# RogoIR.net
KiCad netlist of a schematic drawn in Altium Designer
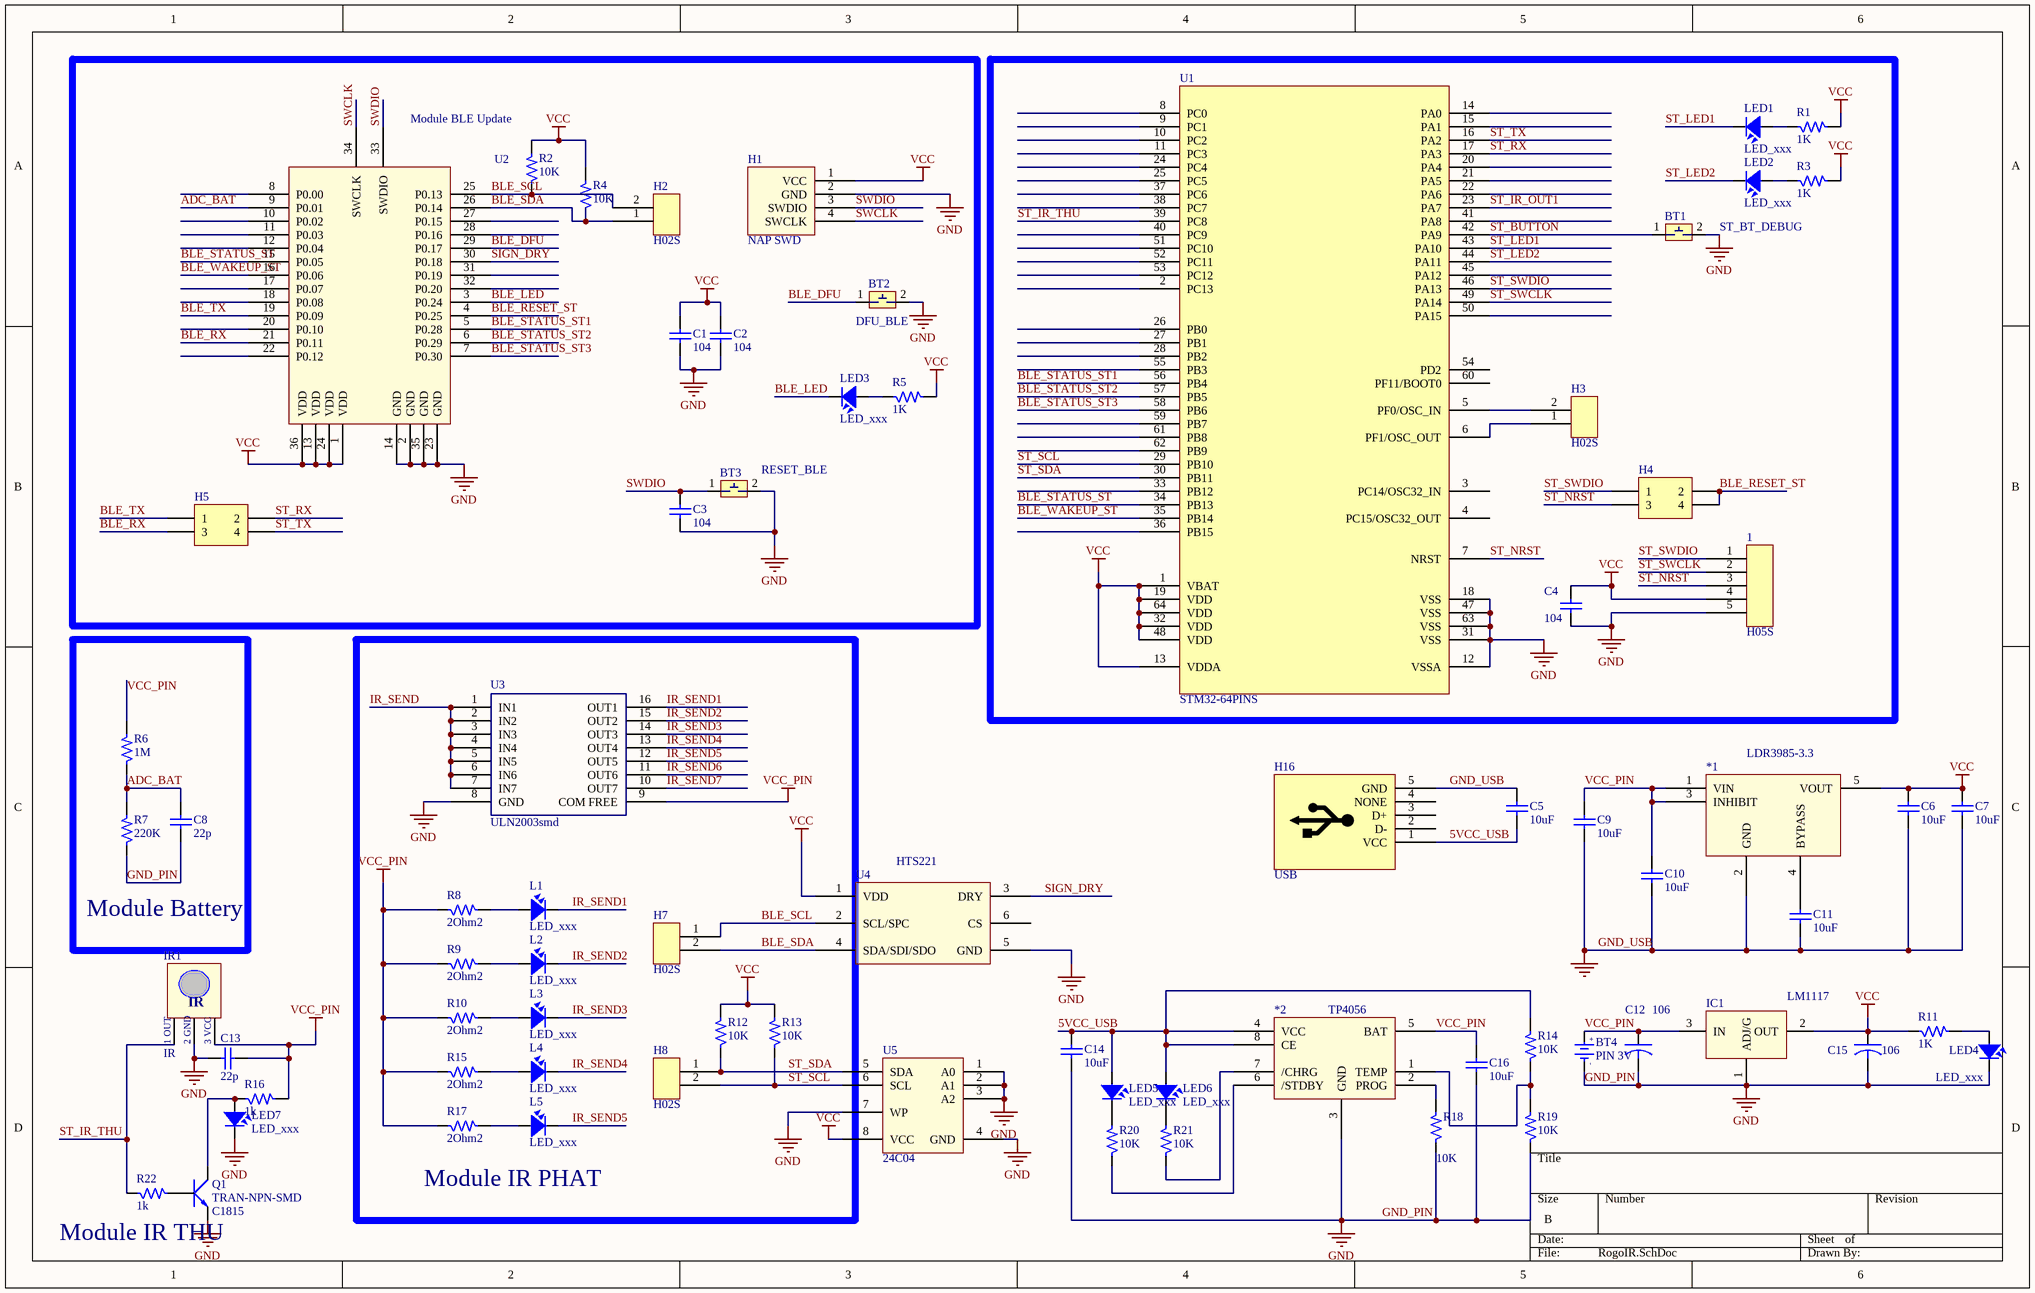
[diagram p0: RogoIR.SchDoc]

(export (version "E")
  (design (tool "Eeschema 10.0.6"))
  (components
    (comp (ref "*1")
      (value "LDR3985-3.3")
      (footprint "LDR3985-3.3")
      (libsource (lib "AngleVu") (part "LDR3985-3.3"))
    )
    (comp (ref "*2") (value "TP4056") (footprint "TP4056") (libsource (lib "AngleVu") (part "TP4056")))
    (comp (ref "1")
      (value "H05S")
      (footprint "H05SA")
      (description "HEADER, SINGLE")
      (libsource (lib "AngleVu") (part "H05S"))
    )
    (comp (ref "BT1")
      (value "ST_BT_DEBUG")
      (footprint "SW2-SMD")
      (libsource (lib "BNTLIB") (part "BUTTON 2 PIN"))
    )
    (comp (ref "BT2")
      (value "DFU_BLE")
      (footprint "SW2-SMD")
      (libsource (lib "BNTLIB") (part "BUTTON 2 PIN"))
    )
    (comp (ref "BT3")
      (value "RESET_BLE")
      (footprint "SW2-SMD")
      (libsource (lib "BNTLIB") (part "BUTTON 2 PIN"))
    )
    (comp (ref "BT4")
      (value "PIN 3V")
      (footprint "H02MA")
      (description "Battery 3VDC")
      (libsource (lib "BNTLIB") (part "PIN 3V"))
    )
    (comp (ref "C1") (value "104") (footprint "0805") (libsource (lib "BNTLIB") (part "Cap")))
    (comp (ref "C2") (value "104") (footprint "0805") (libsource (lib "BNTLIB") (part "Cap")))
    (comp (ref "C3") (value "104") (footprint "0805") (libsource (lib "BNTLIB") (part "Cap")))
    (comp (ref "C4") (value "104") (footprint "0805") (libsource (lib "BNTLIB") (part "Cap")))
    (comp (ref "C5") (value "10uF") (footprint "0805") (libsource (lib "BNTLIB") (part "Cap")))
    (comp (ref "C6") (value "10uF") (footprint "0805") (libsource (lib "BNTLIB") (part "Cap")))
    (comp (ref "C7") (value "10uF") (footprint "0805") (libsource (lib "BNTLIB") (part "Cap")))
    (comp (ref "C8") (value "22p") (footprint "0805") (libsource (lib "BNTLIB") (part "Cap")))
    (comp (ref "C9") (value "10uF") (footprint "0805") (libsource (lib "BNTLIB") (part "Cap")))
    (comp (ref "C10") (value "10uF") (footprint "0805") (libsource (lib "BNTLIB") (part "Cap")))
    (comp (ref "C11") (value "10uF") (footprint "0805") (libsource (lib "BNTLIB") (part "Cap")))
    (comp (ref "C12")
      (value "106")
      (footprint "1206")
      (description "Capacitor")
      (libsource (lib "BNTLIB") (part "CAPACITOR"))
    )
    (comp (ref "C13") (value "22p") (footprint "0805") (libsource (lib "BNTLIB") (part "Cap")))
    (comp (ref "C14") (value "10uF") (footprint "0805") (libsource (lib "BNTLIB") (part "Cap")))
    (comp (ref "C15")
      (value "106")
      (footprint "1206")
      (description "Capacitor")
      (libsource (lib "BNTLIB") (part "CAPACITOR"))
    )
    (comp (ref "C16") (value "10uF") (footprint "0805") (libsource (lib "BNTLIB") (part "Cap")))
    (comp (ref "H1") (value "NAP SWD") (footprint "H04SA") (libsource (lib "AngleVu") (part "NAP SWD")))
    (comp (ref "H2")
      (value "H02S")
      (footprint "H02SA")
      (description "HEADER, SINGLE")
      (libsource (lib "") (part "H02S_1"))
    )
    (comp (ref "H3")
      (value "H02S")
      (footprint "H02SA")
      (description "HEADER, SINGLE")
      (libsource (lib "") (part "H02S_1"))
    )
    (comp (ref "H4")
      (value "H04M")
      (footprint "HDR2X2")
      (description "HEADER, DOUBLE")
      (fields (field (name "PUBLISHER") "Altium Limited"))
      (libsource (lib "AngleVu") (part "H04M"))
    )
    (comp (ref "H5")
      (value "H04M")
      (footprint "HDR2X2")
      (description "HEADER, DOUBLE")
      (fields (field (name "PUBLISHER") "Altium Limited"))
      (libsource (lib "AngleVu") (part "H04M"))
    )
    (comp (ref "H7")
      (value "H02S")
      (footprint "H02SA")
      (description "HEADER, SINGLE")
      (libsource (lib "AngleVu") (part "H02S"))
    )
    (comp (ref "H8")
      (value "H02S")
      (footprint "H02SA")
      (description "HEADER, SINGLE")
      (libsource (lib "AngleVu") (part "H02S"))
    )
    (comp (ref "H16")
      (value "USB")
      (footprint "Micro_USB")
      (description "USB conector")
      (libsource (lib "AngleVu") (part "USB"))
    )
    (comp (ref "IC1")
      (value "LM1117")
      (footprint "lm1117-3.3")
      (description "Available in 1.8V, 2.5V, 2.85V, 3.3V, 5V, and  Adjustable Versions")
      (libsource (lib "BNTLIB") (part "LM1117"))
    )
    (comp (ref "IR1")
      (value "IR")
      (footprint "H03SA")
      (description "Receiver Infraed IC")
      (libsource (lib "AngleVu") (part "IR"))
    )
    (comp (ref "L1")
      (value "LED_xxx")
      (footprint "LED_Z5")
      (description "LED Single colour Green and Red")
      (fields (field (name "Comment") "LED_Z5"))
      (libsource (lib "AngleVu") (part "LED_Z5"))
    )
    (comp (ref "L2")
      (value "LED_xxx")
      (footprint "LED_Z5")
      (description "LED Single colour Green and Red")
      (fields (field (name "Comment") "LED_Z5"))
      (libsource (lib "AngleVu") (part "LED_Z5"))
    )
    (comp (ref "L3")
      (value "LED_xxx")
      (footprint "LED_Z5")
      (description "LED Single colour Green and Red")
      (fields (field (name "Comment") "LED_Z5"))
      (libsource (lib "AngleVu") (part "LED_Z5"))
    )
    (comp (ref "L4")
      (value "LED_xxx")
      (footprint "LED_Z5")
      (description "LED Single colour Green and Red")
      (fields (field (name "Comment") "LED_Z5"))
      (libsource (lib "AngleVu") (part "LED_Z5"))
    )
    (comp (ref "L5")
      (value "LED_xxx")
      (footprint "LED_Z5")
      (description "LED Single colour Green and Red")
      (fields (field (name "Comment") "LED_Z5"))
      (libsource (lib "AngleVu") (part "LED_Z5"))
    )
    (comp (ref "LED1")
      (value "LED_xxx")
      (footprint "0805")
      (description "LED Single colour Green and Red")
      (fields (field (name "Comment") "LED"))
      (libsource (lib "AngleVu") (part "LED"))
    )
    (comp (ref "LED2")
      (value "LED_xxx")
      (footprint "0805")
      (description "LED Single colour Green and Red")
      (fields (field (name "Comment") "LED"))
      (libsource (lib "AngleVu") (part "LED"))
    )
    (comp (ref "LED3")
      (value "LED_xxx")
      (footprint "0805")
      (description "LED Single colour Green and Red")
      (fields (field (name "Comment") "LED"))
      (libsource (lib "AngleVu") (part "LED"))
    )
    (comp (ref "LED4")
      (value "LED_xxx")
      (footprint "0805")
      (description "LED Single colour Green and Red")
      (fields (field (name "Comment") "LED"))
      (libsource (lib "AngleVu") (part "LED"))
    )
    (comp (ref "LED5")
      (value "LED_xxx")
      (footprint "0805")
      (description "LED Single colour Green and Red")
      (fields (field (name "Comment") "LED"))
      (libsource (lib "AngleVu") (part "LED"))
    )
    (comp (ref "LED6")
      (value "LED_xxx")
      (footprint "0805")
      (description "LED Single colour Green and Red")
      (fields (field (name "Comment") "LED"))
      (libsource (lib "AngleVu") (part "LED"))
    )
    (comp (ref "LED7")
      (value "LED_xxx")
      (footprint "0805")
      (description "LED Single colour Green and Red")
      (fields (field (name "Comment") "LED"))
      (libsource (lib "AngleVu") (part "LED"))
    )
    (comp (ref "Q1")
      (value "TRAN-NPN-SMD")
      (footprint "TRAN-NPN-SMD")
      (description "NPN 600mW, ECB")
      (fields (field (name "ALTIUM_VALUE") "C1815"))
      (libsource (lib "AngleVu") (part "TRAN-NPN-SMD"))
    )
    (comp (ref "R1")
      (value "1K")
      (footprint "0805")
      (description "Resistor 1/4W")
      (libsource (lib "BNTLIB") (part "Res"))
    )
    (comp (ref "R2")
      (value "10K")
      (footprint "0805")
      (description "Resistor 1/4W")
      (fields (field (name "Comment") "RESISTOR"))
      (libsource (lib "AngleVu") (part "RESISTOR"))
    )
    (comp (ref "R3")
      (value "1K")
      (footprint "0805")
      (description "Resistor 1/4W")
      (libsource (lib "BNTLIB") (part "Res"))
    )
    (comp (ref "R4")
      (value "10K")
      (footprint "0805")
      (description "Resistor 1/4W")
      (fields (field (name "Comment") "RESISTOR"))
      (libsource (lib "AngleVu") (part "RESISTOR"))
    )
    (comp (ref "R5")
      (value "1K")
      (footprint "0805")
      (description "Resistor 1/4W")
      (libsource (lib "BNTLIB") (part "Res"))
    )
    (comp (ref "R6")
      (value "1M")
      (footprint "0805")
      (description "Resistor 1/4W")
      (libsource (lib "BNTLIB") (part "Res"))
    )
    (comp (ref "R7")
      (value "220K")
      (footprint "0805")
      (description "Resistor 1/4W")
      (libsource (lib "BNTLIB") (part "Res"))
    )
    (comp (ref "R8")
      (value "2Ohm2")
      (footprint "0805")
      (description "Resistor 1/4W")
      (libsource (lib "BNTLIB") (part "Res"))
    )
    (comp (ref "R9")
      (value "2Ohm2")
      (footprint "0805")
      (description "Resistor 1/4W")
      (libsource (lib "BNTLIB") (part "Res"))
    )
    (comp (ref "R10")
      (value "2Ohm2")
      (footprint "0805")
      (description "Resistor 1/4W")
      (libsource (lib "BNTLIB") (part "Res"))
    )
    (comp (ref "R11")
      (value "1K")
      (footprint "0805")
      (description "Resistor 1/4W")
      (libsource (lib "BNTLIB") (part "Res"))
    )
    (comp (ref "R12")
      (value "10K")
      (footprint "0805")
      (description "Resistor 1/4W")
      (fields (field (name "Comment") "RESISTOR"))
      (libsource (lib "AngleVu") (part "RESISTOR"))
    )
    (comp (ref "R13")
      (value "10K")
      (footprint "0805")
      (description "Resistor 1/4W")
      (fields (field (name "Comment") "RESISTOR"))
      (libsource (lib "AngleVu") (part "RESISTOR"))
    )
    (comp (ref "R14")
      (value "10K")
      (footprint "0805")
      (description "Resistor 1/4W")
      (fields (field (name "Comment") "RESISTOR"))
      (libsource (lib "AngleVu") (part "RESISTOR"))
    )
    (comp (ref "R15")
      (value "2Ohm2")
      (footprint "0805")
      (description "Resistor 1/4W")
      (libsource (lib "BNTLIB") (part "Res"))
    )
    (comp (ref "R16")
      (value "1k")
      (footprint "0805")
      (description "Resistor 1/4W")
      (libsource (lib "BNTLIB") (part "Res"))
    )
    (comp (ref "R17")
      (value "2Ohm2")
      (footprint "0805")
      (description "Resistor 1/4W")
      (libsource (lib "BNTLIB") (part "Res"))
    )
    (comp (ref "R18")
      (value "10K")
      (footprint "0805")
      (description "Resistor 1/4W")
      (fields (field (name "Comment") "RESISTOR"))
      (libsource (lib "AngleVu") (part "RESISTOR"))
    )
    (comp (ref "R19")
      (value "10K")
      (footprint "0805")
      (description "Resistor 1/4W")
      (fields (field (name "Comment") "RESISTOR"))
      (libsource (lib "AngleVu") (part "RESISTOR"))
    )
    (comp (ref "R20")
      (value "10K")
      (footprint "0805")
      (description "Resistor 1/4W")
      (fields (field (name "Comment") "RESISTOR"))
      (libsource (lib "AngleVu") (part "RESISTOR"))
    )
    (comp (ref "R21")
      (value "10K")
      (footprint "0805")
      (description "Resistor 1/4W")
      (fields (field (name "Comment") "RESISTOR"))
      (libsource (lib "AngleVu") (part "RESISTOR"))
    )
    (comp (ref "R22")
      (value "1k")
      (footprint "0805")
      (description "Resistor 1/4W")
      (libsource (lib "BNTLIB") (part "Res"))
    )
    (comp (ref "U1")
      (value "STM32-64PINS")
      (footprint "LQFP64Pins")
      (libsource (lib "AngleVu") (part "STM32-64PINS"))
    )
    (comp (ref "U2")
      (value "Module BLE Update")
      (footprint "Module Ble")
      (libsource (lib "AngleVu") (part "Module BLE Update"))
    )
    (comp (ref "U3")
      (value "ULN2003smd")
      (footprint "ULN2003-smd16P")
      (libsource (lib "AngleVu") (part "ULN2003smd"))
    )
    (comp (ref "U4") (value "HTS221") (footprint "HTS221") (libsource (lib "AngleVu") (part "HTS221")))
    (comp (ref "U5") (value "24C04") (footprint "24C04SOIC") (libsource (lib "AngleVu") (part "24C04")))
  )
  (nets
    (net (code "1") (name "/5VCC_USB") (class "Default")
      (node (ref "*2") (pin "4") (pinfunction "VCC_4") (pintype "passive"))
      (node (ref "*2") (pin "8") (pinfunction "CE_8") (pintype "passive"))
      (node (ref "C14") (pin "1") (pinfunction "1_1") (pintype "passive"))
      (node (ref "C5") (pin "2") (pinfunction "2_2") (pintype "passive"))
      (node (ref "H16") (pin "1") (pinfunction "VCC_1") (pintype "passive"))
      (node (ref "LED5") (pin "1") (pinfunction "1_1") (pintype "passive"))
      (node (ref "LED6") (pin "1") (pinfunction "1_1") (pintype "passive"))
      (node (ref "R14") (pin "2") (pinfunction "2_2") (pintype "passive"))
    )
    (net (code "2") (name "/ADC_BAT") (class "Default")
      (node (ref "C8") (pin "2") (pinfunction "2_2") (pintype "passive"))
      (node (ref "R6") (pin "1") (pinfunction "1_1") (pintype "passive"))
      (node (ref "R7") (pin "2") (pinfunction "2_2") (pintype "passive"))
      (node (ref "U2") (pin "9") (pinfunction "P0.01_9") (pintype "passive"))
    )
    (net (code "3") (name "/BLE_DFU") (class "Default")
      (node (ref "BT2") (pin "1") (pinfunction "1_1") (pintype "passive"))
      (node (ref "U2") (pin "29") (pinfunction "P0.17_29") (pintype "passive"))
    )
    (net (code "4") (name "/BLE_LED") (class "Default")
      (node (ref "LED3") (pin "2") (pinfunction "2_2") (pintype "passive"))
      (node (ref "U2") (pin "3") (pinfunction "P0.24_3") (pintype "passive"))
    )
    (net (code "5") (name "/BLE_RESET_ST") (class "Default")
      (node (ref "H4") (pin "2") (pinfunction "2_2") (pintype "passive"))
      (node (ref "H4") (pin "4") (pinfunction "4_4") (pintype "passive"))
      (node (ref "U2") (pin "4") (pinfunction "P0.25_4") (pintype "passive"))
    )
    (net (code "6") (name "/BLE_RX") (class "Default")
      (node (ref "H5") (pin "3") (pinfunction "3_3") (pintype "passive"))
      (node (ref "U2") (pin "21") (pinfunction "P0.11_21") (pintype "passive"))
    )
    (net (code "7") (name "/BLE_SCL") (class "Default")
      (node (ref "H2") (pin "2") (pintype "passive"))
      (node (ref "H7") (pin "1") (pintype "passive"))
      (node (ref "R2") (pin "1") (pinfunction "1_1") (pintype "passive"))
      (node (ref "U2") (pin "25") (pinfunction "P0.13_25") (pintype "passive"))
      (node (ref "U4") (pin "2") (pinfunction "SCL/SPC_2") (pintype "passive"))
    )
    (net (code "8") (name "/BLE_SDA") (class "Default")
      (node (ref "H2") (pin "1") (pintype "passive"))
      (node (ref "H7") (pin "2") (pintype "passive"))
      (node (ref "R4") (pin "1") (pinfunction "1_1") (pintype "passive"))
      (node (ref "U2") (pin "26") (pinfunction "P0.14_26") (pintype "passive"))
      (node (ref "U4") (pin "4") (pinfunction "SDA/SDI/SDO_4") (pintype "passive"))
    )
    (net (code "9") (name "/BLE_STATUS_ST") (class "Default")
      (node (ref "U1") (pin "34") (pinfunction "PB13_34") (pintype "passive"))
      (node (ref "U2") (pin "15") (pinfunction "P0.05_15") (pintype "passive"))
    )
    (net (code "10") (name "/BLE_STATUS_ST1") (class "Default")
      (node (ref "U1") (pin "56") (pinfunction "PB4_56") (pintype "passive"))
      (node (ref "U2") (pin "5") (pinfunction "P0.28_5") (pintype "passive"))
    )
    (net (code "11") (name "/BLE_STATUS_ST2") (class "Default")
      (node (ref "U1") (pin "57") (pinfunction "PB5_57") (pintype "passive"))
      (node (ref "U2") (pin "6") (pinfunction "P0.29_6") (pintype "passive"))
    )
    (net (code "12") (name "/BLE_STATUS_ST3") (class "Default")
      (node (ref "U1") (pin "58") (pinfunction "PB6_58") (pintype "passive"))
      (node (ref "U2") (pin "7") (pinfunction "P0.30_7") (pintype "passive"))
    )
    (net (code "13") (name "/BLE_TX") (class "Default")
      (node (ref "H5") (pin "1") (pinfunction "1_1") (pintype "passive"))
      (node (ref "U2") (pin "19") (pinfunction "P0.09_19") (pintype "passive"))
    )
    (net (code "14") (name "/BLE_WAKEUP_ST") (class "Default")
      (node (ref "U1") (pin "35") (pinfunction "PB14_35") (pintype "passive"))
      (node (ref "U2") (pin "16") (pinfunction "P0.06_16") (pintype "passive"))
    )
    (net (code "15") (name "/IR_SEND") (class "Default")
      (node (ref "U3") (pin "1") (pinfunction "IN1_1") (pintype "passive"))
      (node (ref "U3") (pin "2") (pinfunction "IN2_2") (pintype "passive"))
      (node (ref "U3") (pin "3") (pinfunction "IN3_3") (pintype "passive"))
      (node (ref "U3") (pin "4") (pinfunction "IN4_4") (pintype "passive"))
      (node (ref "U3") (pin "5") (pinfunction "IN5_5") (pintype "passive"))
      (node (ref "U3") (pin "6") (pinfunction "IN6_6") (pintype "passive"))
      (node (ref "U3") (pin "7") (pinfunction "IN7_7") (pintype "passive"))
    )
    (net (code "16") (name "/IR_SEND1") (class "Default")
      (node (ref "L1") (pin "2") (pinfunction "2_2") (pintype "passive"))
      (node (ref "U3") (pin "16") (pinfunction "OUT1_16") (pintype "passive"))
    )
    (net (code "17") (name "/IR_SEND2") (class "Default")
      (node (ref "L2") (pin "2") (pinfunction "2_2") (pintype "passive"))
      (node (ref "U3") (pin "15") (pinfunction "OUT2_15") (pintype "passive"))
    )
    (net (code "18") (name "/IR_SEND3") (class "Default")
      (node (ref "L3") (pin "2") (pinfunction "2_2") (pintype "passive"))
      (node (ref "U3") (pin "14") (pinfunction "OUT3_14") (pintype "passive"))
    )
    (net (code "19") (name "/IR_SEND4") (class "Default")
      (node (ref "L4") (pin "2") (pinfunction "2_2") (pintype "passive"))
      (node (ref "U3") (pin "13") (pinfunction "OUT4_13") (pintype "passive"))
    )
    (net (code "20") (name "/IR_SEND5") (class "Default")
      (node (ref "L5") (pin "2") (pinfunction "2_2") (pintype "passive"))
      (node (ref "U3") (pin "12") (pinfunction "OUT5_12") (pintype "passive"))
    )
    (net (code "21") (name "/IR_SEND6") (class "Default")
      (node (ref "U3") (pin "11") (pinfunction "OUT6_11") (pintype "passive"))
    )
    (net (code "22") (name "/IR_SEND7") (class "Default")
      (node (ref "U3") (pin "10") (pinfunction "OUT7_10") (pintype "passive"))
    )
    (net (code "23") (name "/SIGN_DRY") (class "Default")
      (node (ref "U2") (pin "30") (pinfunction "P0.18_30") (pintype "passive"))
      (node (ref "U4") (pin "3") (pinfunction "DRY_3") (pintype "passive"))
    )
    (net (code "24") (name "/ST_BUTTON") (class "Default")
      (node (ref "BT1") (pin "1") (pinfunction "1_1") (pintype "passive"))
      (node (ref "U1") (pin "42") (pinfunction "PA9_42") (pintype "passive"))
    )
    (net (code "25") (name "/ST_IR_OUT1") (class "Default")
      (node (ref "U1") (pin "23") (pinfunction "PA7_23") (pintype "passive"))
    )
    (net (code "26") (name "/ST_IR_THU") (class "Default")
      (node (ref "IR1") (pin "1") (pinfunction "Out_1") (pintype "passive"))
      (node (ref "R22") (pin "1") (pinfunction "1_1") (pintype "passive"))
      (node (ref "U1") (pin "39") (pinfunction "PC8_39") (pintype "passive"))
    )
    (net (code "27") (name "/ST_LED1") (class "Default")
      (node (ref "LED1") (pin "2") (pinfunction "2_2") (pintype "passive"))
      (node (ref "U1") (pin "43") (pinfunction "PA10_43") (pintype "passive"))
    )
    (net (code "28") (name "/ST_LED2") (class "Default")
      (node (ref "LED2") (pin "2") (pinfunction "2_2") (pintype "passive"))
      (node (ref "U1") (pin "44") (pinfunction "PA11_44") (pintype "passive"))
    )
    (net (code "29") (name "/ST_NRST") (class "Default")
      (node (ref "1") (pin "3") (pintype "passive"))
      (node (ref "H4") (pin "3") (pinfunction "3_3") (pintype "passive"))
      (node (ref "U1") (pin "7") (pinfunction "NRST_7") (pintype "passive"))
    )
    (net (code "30") (name "/ST_RX") (class "Default")
      (node (ref "H5") (pin "2") (pinfunction "2_2") (pintype "passive"))
      (node (ref "U1") (pin "17") (pinfunction "PA3_17") (pintype "passive"))
    )
    (net (code "31") (name "/ST_SCL") (class "Default")
      (node (ref "H8") (pin "2") (pintype "passive"))
      (node (ref "R13") (pin "1") (pinfunction "1_1") (pintype "passive"))
      (node (ref "U1") (pin "29") (pinfunction "PB10_29") (pintype "passive"))
      (node (ref "U5") (pin "6") (pinfunction "SCL_6") (pintype "passive"))
    )
    (net (code "32") (name "/ST_SDA") (class "Default")
      (node (ref "H8") (pin "1") (pintype "passive"))
      (node (ref "R12") (pin "1") (pinfunction "1_1") (pintype "passive"))
      (node (ref "U1") (pin "30") (pinfunction "PB11_30") (pintype "passive"))
      (node (ref "U5") (pin "5") (pinfunction "SDA_5") (pintype "passive"))
    )
    (net (code "33") (name "/ST_SWCLK") (class "Default")
      (node (ref "1") (pin "2") (pintype "passive"))
      (node (ref "U1") (pin "49") (pinfunction "PA14_49") (pintype "passive"))
    )
    (net (code "34") (name "/ST_SWDIO") (class "Default")
      (node (ref "1") (pin "1") (pintype "passive"))
      (node (ref "H4") (pin "1") (pinfunction "1_1") (pintype "passive"))
      (node (ref "U1") (pin "46") (pinfunction "PA13_46") (pintype "passive"))
    )
    (net (code "35") (name "/ST_TX") (class "Default")
      (node (ref "H5") (pin "4") (pinfunction "4_4") (pintype "passive"))
      (node (ref "U1") (pin "16") (pinfunction "PA2_16") (pintype "passive"))
    )
    (net (code "36") (name "/SWCLK") (class "Default")
      (node (ref "H1") (pin "4") (pinfunction "SWCLK_4") (pintype "passive"))
      (node (ref "U2") (pin "34") (pinfunction "SWCLK_34") (pintype "passive"))
    )
    (net (code "37") (name "/SWDIO") (class "Default")
      (node (ref "BT3") (pin "1") (pinfunction "1_1") (pintype "passive"))
      (node (ref "C3") (pin "1") (pinfunction "1_1") (pintype "passive"))
      (node (ref "H1") (pin "3") (pinfunction "SWDIO_3") (pintype "passive"))
      (node (ref "U2") (pin "33") (pinfunction "SWDIO_33") (pintype "passive"))
    )
    (net (code "38") (name "GND") (class "Default")
      (node (ref "*1") (pin "2") (pinfunction "GND_2") (pintype "passive"))
      (node (ref "*2") (pin "3") (pinfunction "GND_3") (pintype "passive"))
      (node (ref "1") (pin "5") (pintype "passive"))
      (node (ref "BT1") (pin "2") (pinfunction "2_2") (pintype "passive"))
      (node (ref "BT2") (pin "2") (pinfunction "2_2") (pintype "passive"))
      (node (ref "BT3") (pin "2") (pinfunction "2_2") (pintype "passive"))
      (node (ref "BT4") (pin "2") (pinfunction "GND_2") (pintype "passive"))
      (node (ref "C1") (pin "2") (pinfunction "2_2") (pintype "passive"))
      (node (ref "C10") (pin "2") (pinfunction "2_2") (pintype "passive"))
      (node (ref "C11") (pin "2") (pinfunction "2_2") (pintype "passive"))
      (node (ref "C12") (pin "2") (pinfunction "2_2") (pintype "passive"))
      (node (ref "C13") (pin "2") (pinfunction "2_2") (pintype "passive"))
      (node (ref "C14") (pin "2") (pinfunction "2_2") (pintype "passive"))
      (node (ref "C15") (pin "2") (pinfunction "2_2") (pintype "passive"))
      (node (ref "C16") (pin "2") (pinfunction "2_2") (pintype "passive"))
      (node (ref "C2") (pin "2") (pinfunction "2_2") (pintype "passive"))
      (node (ref "C3") (pin "2") (pinfunction "2_2") (pintype "passive"))
      (node (ref "C4") (pin "2") (pinfunction "2_2") (pintype "passive"))
      (node (ref "C5") (pin "1") (pinfunction "1_1") (pintype "passive"))
      (node (ref "C6") (pin "2") (pinfunction "2_2") (pintype "passive"))
      (node (ref "C7") (pin "2") (pinfunction "2_2") (pintype "passive"))
      (node (ref "C8") (pin "1") (pinfunction "1_1") (pintype "passive"))
      (node (ref "C9") (pin "2") (pinfunction "2_2") (pintype "passive"))
      (node (ref "H1") (pin "2") (pinfunction "GND_2") (pintype "passive"))
      (node (ref "H16") (pin "5") (pinfunction "GND_5") (pintype "passive"))
      (node (ref "IC1") (pin "1") (pinfunction "ADJ/G_1") (pintype "passive"))
      (node (ref "IR1") (pin "2") (pinfunction "GND_2") (pintype "passive"))
      (node (ref "LED4") (pin "2") (pinfunction "2_2") (pintype "passive"))
      (node (ref "LED7") (pin "2") (pinfunction "2_2") (pintype "passive"))
      (node (ref "Q1") (pin "2") (pinfunction "E_2") (pintype "passive"))
      (node (ref "R18") (pin "1") (pinfunction "1_1") (pintype "passive"))
      (node (ref "R19") (pin "1") (pinfunction "1_1") (pintype "passive"))
      (node (ref "R7") (pin "1") (pinfunction "1_1") (pintype "passive"))
      (node (ref "U1") (pin "12") (pinfunction "VSSA_12") (pintype "passive"))
      (node (ref "U1") (pin "18") (pinfunction "VSS_18") (pintype "passive"))
      (node (ref "U1") (pin "31") (pinfunction "VSS_31") (pintype "passive"))
      (node (ref "U1") (pin "47") (pinfunction "VSS_47") (pintype "passive"))
      (node (ref "U1") (pin "63") (pinfunction "VSS_63") (pintype "passive"))
      (node (ref "U2") (pin "14") (pinfunction "GND_14") (pintype "passive"))
      (node (ref "U2") (pin "2") (pinfunction "GND_2") (pintype "passive"))
      (node (ref "U2") (pin "23") (pinfunction "GND_23") (pintype "passive"))
      (node (ref "U2") (pin "35") (pinfunction "GND_35") (pintype "passive"))
      (node (ref "U3") (pin "8") (pinfunction "GND_8") (pintype "passive"))
      (node (ref "U4") (pin "5") (pinfunction "GND_5") (pintype "passive"))
      (node (ref "U5") (pin "1") (pinfunction "A0_1") (pintype "passive"))
      (node (ref "U5") (pin "2") (pinfunction "A1_2") (pintype "passive"))
      (node (ref "U5") (pin "3") (pinfunction "A2_3") (pintype "passive"))
      (node (ref "U5") (pin "4") (pinfunction "GND_4") (pintype "passive"))
      (node (ref "U5") (pin "7") (pinfunction "WP_7") (pintype "passive"))
    )
    (net (code "39") (name "Net-(*1-BYPASS)") (class "Default")
      (node (ref "*1") (pin "4") (pinfunction "BYPASS_4") (pintype "passive"))
      (node (ref "C11") (pin "1") (pinfunction "1_1") (pintype "passive"))
    )
    (net (code "40") (name "Net-(*2-PROG)") (class "Default")
      (node (ref "*2") (pin "2") (pinfunction "PROG_2") (pintype "passive"))
      (node (ref "R18") (pin "2") (pinfunction "2_2") (pintype "passive"))
    )
    (net (code "41") (name "Net-(*2-TEMP)") (class "Default")
      (node (ref "*2") (pin "1") (pinfunction "TEMP_1") (pintype "passive"))
      (node (ref "R14") (pin "1") (pinfunction "1_1") (pintype "passive"))
      (node (ref "R19") (pin "2") (pinfunction "2_2") (pintype "passive"))
    )
    (net (code "42") (name "Net-(*2-{slash}CHRG)") (class "Default")
      (node (ref "*2") (pin "7") (pinfunction "/CHRG_7") (pintype "passive"))
      (node (ref "R21") (pin "1") (pinfunction "1_1") (pintype "passive"))
    )
    (net (code "43") (name "Net-(*2-{slash}STDBY)") (class "Default")
      (node (ref "*2") (pin "6") (pinfunction "/STDBY_6") (pintype "passive"))
      (node (ref "R20") (pin "1") (pinfunction "1_1") (pintype "passive"))
    )
    (net (code "44") (name "Net-(L1-Pad1)") (class "Default")
      (node (ref "L1") (pin "1") (pinfunction "1_1") (pintype "passive"))
      (node (ref "R8") (pin "2") (pinfunction "2_2") (pintype "passive"))
    )
    (net (code "45") (name "Net-(L2-Pad1)") (class "Default")
      (node (ref "L2") (pin "1") (pinfunction "1_1") (pintype "passive"))
      (node (ref "R9") (pin "2") (pinfunction "2_2") (pintype "passive"))
    )
    (net (code "46") (name "Net-(L3-Pad1)") (class "Default")
      (node (ref "L3") (pin "1") (pinfunction "1_1") (pintype "passive"))
      (node (ref "R10") (pin "2") (pinfunction "2_2") (pintype "passive"))
    )
    (net (code "47") (name "Net-(L4-Pad1)") (class "Default")
      (node (ref "L4") (pin "1") (pinfunction "1_1") (pintype "passive"))
      (node (ref "R15") (pin "2") (pinfunction "2_2") (pintype "passive"))
    )
    (net (code "48") (name "Net-(L5-Pad1)") (class "Default")
      (node (ref "L5") (pin "1") (pinfunction "1_1") (pintype "passive"))
      (node (ref "R17") (pin "2") (pinfunction "2_2") (pintype "passive"))
    )
    (net (code "49") (name "Net-(LED1-Pad1)") (class "Default")
      (node (ref "LED1") (pin "1") (pinfunction "1_1") (pintype "passive"))
      (node (ref "R1") (pin "1") (pinfunction "1_1") (pintype "passive"))
    )
    (net (code "50") (name "Net-(LED2-Pad1)") (class "Default")
      (node (ref "LED2") (pin "1") (pinfunction "1_1") (pintype "passive"))
      (node (ref "R3") (pin "1") (pinfunction "1_1") (pintype "passive"))
    )
    (net (code "51") (name "Net-(LED3-Pad1)") (class "Default")
      (node (ref "LED3") (pin "1") (pinfunction "1_1") (pintype "passive"))
      (node (ref "R5") (pin "1") (pinfunction "1_1") (pintype "passive"))
    )
    (net (code "52") (name "Net-(LED4-Pad1)") (class "Default")
      (node (ref "LED4") (pin "1") (pinfunction "1_1") (pintype "passive"))
      (node (ref "R11") (pin "2") (pinfunction "2_2") (pintype "passive"))
    )
    (net (code "53") (name "Net-(LED5-Pad2)") (class "Default")
      (node (ref "LED5") (pin "2") (pinfunction "2_2") (pintype "passive"))
      (node (ref "R20") (pin "2") (pinfunction "2_2") (pintype "passive"))
    )
    (net (code "54") (name "Net-(LED6-Pad2)") (class "Default")
      (node (ref "LED6") (pin "2") (pinfunction "2_2") (pintype "passive"))
      (node (ref "R21") (pin "2") (pinfunction "2_2") (pintype "passive"))
    )
    (net (code "55") (name "Net-(Q1-B)") (class "Default")
      (node (ref "Q1") (pin "1") (pinfunction "B_1") (pintype "passive"))
      (node (ref "R22") (pin "2") (pinfunction "2_2") (pintype "passive"))
    )
    (net (code "56") (name "Net-(Q1-C)") (class "Default")
      (node (ref "LED7") (pin "1") (pinfunction "1_1") (pintype "passive"))
      (node (ref "Q1") (pin "3") (pinfunction "C_3") (pintype "passive"))
      (node (ref "R16") (pin "1") (pinfunction "1_1") (pintype "passive"))
    )
    (net (code "57") (name "Net-(U1-PF0{slash}OSC_IN)") (class "Default")
      (node (ref "H3") (pin "2") (pintype "passive"))
      (node (ref "U1") (pin "5") (pinfunction "PF0/OSC_IN_5") (pintype "passive"))
    )
    (net (code "58") (name "Net-(U1-PF1{slash}OSC_OUT)") (class "Default")
      (node (ref "H3") (pin "1") (pintype "passive"))
      (node (ref "U1") (pin "6") (pinfunction "PF1/OSC_OUT_6") (pintype "passive"))
    )
    (net (code "59") (name "VCC") (class "Default")
      (node (ref "*1") (pin "5") (pinfunction "VOUT_5") (pintype "passive"))
      (node (ref "1") (pin "4") (pintype "passive"))
      (node (ref "C1") (pin "1") (pinfunction "1_1") (pintype "passive"))
      (node (ref "C15") (pin "1") (pinfunction "1_1") (pintype "passive"))
      (node (ref "C2") (pin "1") (pinfunction "1_1") (pintype "passive"))
      (node (ref "C4") (pin "1") (pinfunction "1_1") (pintype "passive"))
      (node (ref "C6") (pin "1") (pinfunction "1_1") (pintype "passive"))
      (node (ref "C7") (pin "1") (pinfunction "1_1") (pintype "passive"))
      (node (ref "H1") (pin "1") (pinfunction "VCC_1") (pintype "passive"))
      (node (ref "IC1") (pin "2") (pinfunction "OUT_2") (pintype "passive"))
      (node (ref "R1") (pin "2") (pinfunction "2_2") (pintype "passive"))
      (node (ref "R11") (pin "1") (pinfunction "1_1") (pintype "passive"))
      (node (ref "R12") (pin "2") (pinfunction "2_2") (pintype "passive"))
      (node (ref "R13") (pin "2") (pinfunction "2_2") (pintype "passive"))
      (node (ref "R2") (pin "2") (pinfunction "2_2") (pintype "passive"))
      (node (ref "R3") (pin "2") (pinfunction "2_2") (pintype "passive"))
      (node (ref "R4") (pin "2") (pinfunction "2_2") (pintype "passive"))
      (node (ref "R5") (pin "2") (pinfunction "2_2") (pintype "passive"))
      (node (ref "U1") (pin "1") (pinfunction "VBAT_1") (pintype "passive"))
      (node (ref "U1") (pin "13") (pinfunction "VDDA_13") (pintype "passive"))
      (node (ref "U1") (pin "19") (pinfunction "VDD_19") (pintype "passive"))
      (node (ref "U1") (pin "32") (pinfunction "VDD_32") (pintype "passive"))
      (node (ref "U1") (pin "48") (pinfunction "VDD_48") (pintype "passive"))
      (node (ref "U1") (pin "64") (pinfunction "VDD_64") (pintype "passive"))
      (node (ref "U2") (pin "1") (pinfunction "VDD_1") (pintype "passive"))
      (node (ref "U2") (pin "13") (pinfunction "VDD_13") (pintype "passive"))
      (node (ref "U2") (pin "24") (pinfunction "VDD_24") (pintype "passive"))
      (node (ref "U2") (pin "36") (pinfunction "VDD_36") (pintype "passive"))
      (node (ref "U4") (pin "1") (pinfunction "VDD_1") (pintype "passive"))
      (node (ref "U5") (pin "8") (pinfunction "VCC_8") (pintype "passive"))
    )
    (net (code "60") (name "VCC_PIN") (class "Default")
      (node (ref "*1") (pin "1") (pinfunction "VIN_1") (pintype "passive"))
      (node (ref "*1") (pin "3") (pinfunction "INHIBIT_3") (pintype "passive"))
      (node (ref "*2") (pin "5") (pinfunction "BAT_5") (pintype "passive"))
      (node (ref "BT4") (pin "1") (pinfunction "+3V_1") (pintype "passive"))
      (node (ref "C10") (pin "1") (pinfunction "1_1") (pintype "passive"))
      (node (ref "C12") (pin "1") (pinfunction "1_1") (pintype "passive"))
      (node (ref "C13") (pin "1") (pinfunction "1_1") (pintype "passive"))
      (node (ref "C16") (pin "1") (pinfunction "1_1") (pintype "passive"))
      (node (ref "C9") (pin "1") (pinfunction "1_1") (pintype "passive"))
      (node (ref "IC1") (pin "3") (pinfunction "IN_3") (pintype "passive"))
      (node (ref "IR1") (pin "3") (pinfunction "VCC_3") (pintype "passive"))
      (node (ref "R10") (pin "1") (pinfunction "1_1") (pintype "passive"))
      (node (ref "R15") (pin "1") (pinfunction "1_1") (pintype "passive"))
      (node (ref "R16") (pin "2") (pinfunction "2_2") (pintype "passive"))
      (node (ref "R17") (pin "1") (pinfunction "1_1") (pintype "passive"))
      (node (ref "R6") (pin "2") (pinfunction "2_2") (pintype "passive"))
      (node (ref "R8") (pin "1") (pinfunction "1_1") (pintype "passive"))
      (node (ref "R9") (pin "1") (pinfunction "1_1") (pintype "passive"))
      (node (ref "U3") (pin "9") (pinfunction "COM_FREE_9") (pintype "passive"))
    )
    (net (code "61") (name "unconnected-(H16-6-Pad0)") (class "Default")
      (node (ref "H16") (pin "0") (pinfunction "6_0") (pintype "passive"))
    )
    (net (code "62") (name "unconnected-(H16-D+-Pad3)") (class "Default")
      (node (ref "H16") (pin "3") (pinfunction "D+_3") (pintype "passive"))
    )
    (net (code "63") (name "unconnected-(H16-D--Pad2)") (class "Default")
      (node (ref "H16") (pin "2") (pinfunction "D-_2") (pintype "passive"))
    )
    (net (code "64") (name "unconnected-(H16-NONE-Pad4)") (class "Default")
      (node (ref "H16") (pin "4") (pinfunction "NONE_4") (pintype "passive"))
    )
    (net (code "65") (name "unconnected-(U1-PA0-Pad14)") (class "Default")
      (node (ref "U1") (pin "14") (pinfunction "PA0_14") (pintype "passive"))
    )
    (net (code "66") (name "unconnected-(U1-PA1-Pad15)") (class "Default")
      (node (ref "U1") (pin "15") (pinfunction "PA1_15") (pintype "passive"))
    )
    (net (code "67") (name "unconnected-(U1-PA4-Pad20)") (class "Default")
      (node (ref "U1") (pin "20") (pinfunction "PA4_20") (pintype "passive"))
    )
    (net (code "68") (name "unconnected-(U1-PA5-Pad21)") (class "Default")
      (node (ref "U1") (pin "21") (pinfunction "PA5_21") (pintype "passive"))
    )
    (net (code "69") (name "unconnected-(U1-PA6-Pad22)") (class "Default")
      (node (ref "U1") (pin "22") (pinfunction "PA6_22") (pintype "passive"))
    )
    (net (code "70") (name "unconnected-(U1-PA8-Pad41)") (class "Default")
      (node (ref "U1") (pin "41") (pinfunction "PA8_41") (pintype "passive"))
    )
    (net (code "71") (name "unconnected-(U1-PA12-Pad45)") (class "Default")
      (node (ref "U1") (pin "45") (pinfunction "PA12_45") (pintype "passive"))
    )
    (net (code "72") (name "unconnected-(U1-PA15-Pad50)") (class "Default")
      (node (ref "U1") (pin "50") (pinfunction "PA15_50") (pintype "passive"))
    )
    (net (code "73") (name "unconnected-(U1-PB0-Pad26)") (class "Default")
      (node (ref "U1") (pin "26") (pinfunction "PB0_26") (pintype "passive"))
    )
    (net (code "74") (name "unconnected-(U1-PB1-Pad27)") (class "Default")
      (node (ref "U1") (pin "27") (pinfunction "PB1_27") (pintype "passive"))
    )
    (net (code "75") (name "unconnected-(U1-PB2-Pad28)") (class "Default")
      (node (ref "U1") (pin "28") (pinfunction "PB2_28") (pintype "passive"))
    )
    (net (code "76") (name "unconnected-(U1-PB3-Pad55)") (class "Default")
      (node (ref "U1") (pin "55") (pinfunction "PB3_55") (pintype "passive"))
    )
    (net (code "77") (name "unconnected-(U1-PB7-Pad59)") (class "Default")
      (node (ref "U1") (pin "59") (pinfunction "PB7_59") (pintype "passive"))
    )
    (net (code "78") (name "unconnected-(U1-PB8-Pad61)") (class "Default")
      (node (ref "U1") (pin "61") (pinfunction "PB8_61") (pintype "passive"))
    )
    (net (code "79") (name "unconnected-(U1-PB9-Pad62)") (class "Default")
      (node (ref "U1") (pin "62") (pinfunction "PB9_62") (pintype "passive"))
    )
    (net (code "80") (name "unconnected-(U1-PB12-Pad33)") (class "Default")
      (node (ref "U1") (pin "33") (pinfunction "PB12_33") (pintype "passive"))
    )
    (net (code "81") (name "unconnected-(U1-PB15-Pad36)") (class "Default")
      (node (ref "U1") (pin "36") (pinfunction "PB15_36") (pintype "passive"))
    )
    (net (code "82") (name "unconnected-(U1-PC0-Pad8)") (class "Default")
      (node (ref "U1") (pin "8") (pinfunction "PC0_8") (pintype "passive"))
    )
    (net (code "83") (name "unconnected-(U1-PC1-Pad9)") (class "Default")
      (node (ref "U1") (pin "9") (pinfunction "PC1_9") (pintype "passive"))
    )
    (net (code "84") (name "unconnected-(U1-PC2-Pad10)") (class "Default")
      (node (ref "U1") (pin "10") (pinfunction "PC2_10") (pintype "passive"))
    )
    (net (code "85") (name "unconnected-(U1-PC3-Pad11)") (class "Default")
      (node (ref "U1") (pin "11") (pinfunction "PC3_11") (pintype "passive"))
    )
    (net (code "86") (name "unconnected-(U1-PC4-Pad24)") (class "Default")
      (node (ref "U1") (pin "24") (pinfunction "PC4_24") (pintype "passive"))
    )
    (net (code "87") (name "unconnected-(U1-PC5-Pad25)") (class "Default")
      (node (ref "U1") (pin "25") (pinfunction "PC5_25") (pintype "passive"))
    )
    (net (code "88") (name "unconnected-(U1-PC6-Pad37)") (class "Default")
      (node (ref "U1") (pin "37") (pinfunction "PC6_37") (pintype "passive"))
    )
    (net (code "89") (name "unconnected-(U1-PC7-Pad38)") (class "Default")
      (node (ref "U1") (pin "38") (pinfunction "PC7_38") (pintype "passive"))
    )
    (net (code "90") (name "unconnected-(U1-PC9-Pad40)") (class "Default")
      (node (ref "U1") (pin "40") (pinfunction "PC9_40") (pintype "passive"))
    )
    (net (code "91") (name "unconnected-(U1-PC10-Pad51)") (class "Default")
      (node (ref "U1") (pin "51") (pinfunction "PC10_51") (pintype "passive"))
    )
    (net (code "92") (name "unconnected-(U1-PC11-Pad52)") (class "Default")
      (node (ref "U1") (pin "52") (pinfunction "PC11_52") (pintype "passive"))
    )
    (net (code "93") (name "unconnected-(U1-PC12-Pad53)") (class "Default")
      (node (ref "U1") (pin "53") (pinfunction "PC12_53") (pintype "passive"))
    )
    (net (code "94") (name "unconnected-(U1-PC13-Pad2)") (class "Default")
      (node (ref "U1") (pin "2") (pinfunction "PC13_2") (pintype "passive"))
    )
    (net (code "95") (name "unconnected-(U1-PC14{slash}OSC32_IN-Pad3)") (class "Default")
      (node (ref "U1") (pin "3") (pinfunction "PC14/OSC32_IN_3") (pintype "passive"))
    )
    (net (code "96") (name "unconnected-(U1-PC15{slash}OSC32_OUT-Pad4)") (class "Default")
      (node (ref "U1") (pin "4") (pinfunction "PC15/OSC32_OUT_4") (pintype "passive"))
    )
    (net (code "97") (name "unconnected-(U1-PD2-Pad54)") (class "Default")
      (node (ref "U1") (pin "54") (pinfunction "PD2_54") (pintype "passive"))
    )
    (net (code "98") (name "unconnected-(U1-PF11{slash}BOOT0-Pad60)") (class "Default")
      (node (ref "U1") (pin "60") (pinfunction "PF11/BOOT0_60") (pintype "passive"))
    )
    (net (code "99") (name "unconnected-(U2-P0.00-Pad8)") (class "Default")
      (node (ref "U2") (pin "8") (pinfunction "P0.00_8") (pintype "passive"))
    )
    (net (code "100") (name "unconnected-(U2-P0.02-Pad10)") (class "Default")
      (node (ref "U2") (pin "10") (pinfunction "P0.02_10") (pintype "passive"))
    )
    (net (code "101") (name "unconnected-(U2-P0.03-Pad11)") (class "Default")
      (node (ref "U2") (pin "11") (pinfunction "P0.03_11") (pintype "passive"))
    )
    (net (code "102") (name "unconnected-(U2-P0.04-Pad12)") (class "Default")
      (node (ref "U2") (pin "12") (pinfunction "P0.04_12") (pintype "passive"))
    )
    (net (code "103") (name "unconnected-(U2-P0.07-Pad17)") (class "Default")
      (node (ref "U2") (pin "17") (pinfunction "P0.07_17") (pintype "passive"))
    )
    (net (code "104") (name "unconnected-(U2-P0.08-Pad18)") (class "Default")
      (node (ref "U2") (pin "18") (pinfunction "P0.08_18") (pintype "passive"))
    )
    (net (code "105") (name "unconnected-(U2-P0.10-Pad20)") (class "Default")
      (node (ref "U2") (pin "20") (pinfunction "P0.10_20") (pintype "passive"))
    )
    (net (code "106") (name "unconnected-(U2-P0.12-Pad22)") (class "Default")
      (node (ref "U2") (pin "22") (pinfunction "P0.12_22") (pintype "passive"))
    )
    (net (code "107") (name "unconnected-(U2-P0.15-Pad27)") (class "Default")
      (node (ref "U2") (pin "27") (pinfunction "P0.15_27") (pintype "passive"))
    )
    (net (code "108") (name "unconnected-(U2-P0.16-Pad28)") (class "Default")
      (node (ref "U2") (pin "28") (pinfunction "P0.16_28") (pintype "passive"))
    )
    (net (code "109") (name "unconnected-(U2-P0.19-Pad31)") (class "Default")
      (node (ref "U2") (pin "31") (pinfunction "P0.19_31") (pintype "passive"))
    )
    (net (code "110") (name "unconnected-(U2-P0.20-Pad32)") (class "Default")
      (node (ref "U2") (pin "32") (pinfunction "P0.20_32") (pintype "passive"))
    )
    (net (code "111") (name "unconnected-(U4-CS-Pad6)") (class "Default")
      (node (ref "U4") (pin "6") (pinfunction "CS_6") (pintype "passive"))
    )
  )
)
